# V1_0_0.net
KiCad netlist of a schematic drawn in EAGLE
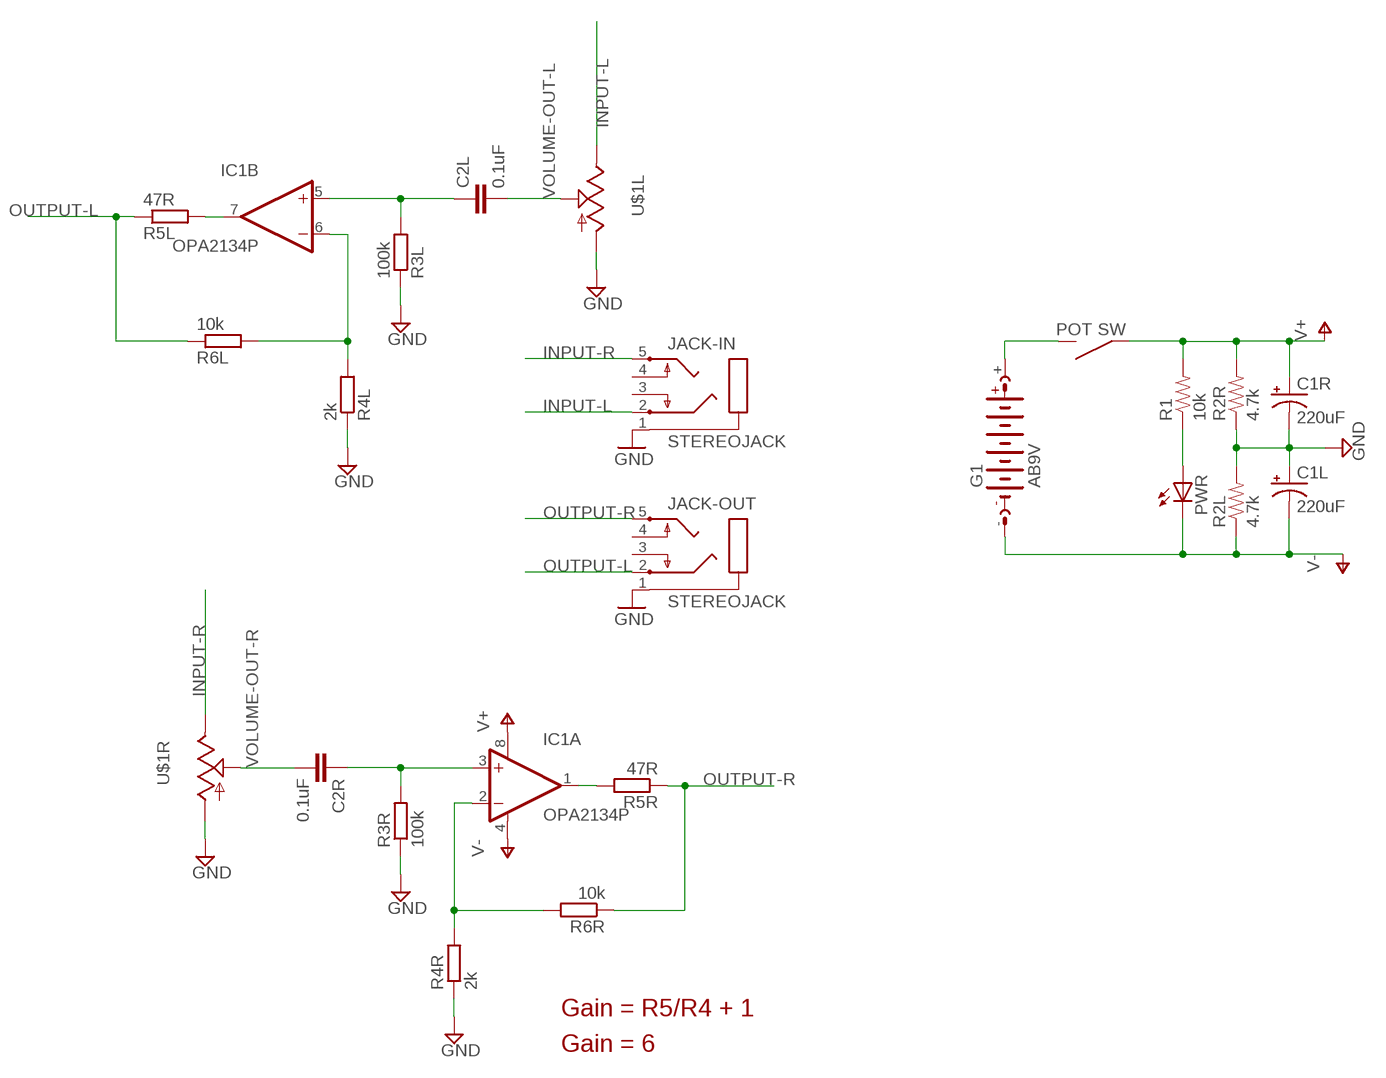
[diagram p0: schematic, sheet 1]

(export (version "E")
  (design (tool "Eeschema 10.0.6"))
  (components
    (comp (ref "C1L")
      (value "220uF")
      (footprint "eagle-import:CPOL-RADIAL-6.3MM")
      (libsource (lib "eagle-import") (part "CAP_POL-RADIAL-6.3MM"))
    )
    (comp (ref "C1R")
      (value "220uF")
      (footprint "eagle-import:CPOL-RADIAL-6.3MM")
      (libsource (lib "eagle-import") (part "CAP_POL-RADIAL-6.3MM"))
    )
    (comp (ref "C2L")
      (value "0.1uF")
      (footprint "eagle-import:C5B5")
      (libsource (lib "eagle-import") (part "C5/5"))
    )
    (comp (ref "C2R")
      (value "0.1uF")
      (footprint "eagle-import:C5B5")
      (libsource (lib "eagle-import") (part "C5/5"))
    )
    (comp (ref "G1")
      (value "AB9V")
      (footprint "eagle-import:AB9V")
      (libsource (lib "eagle-import") (part "AB9V"))
    )
    (comp (ref "IC1")
      (value "OPA2134P")
      (footprint "eagle-import:DIL-8")
      (libsource (lib "eagle-import") (part "OPA2134P"))
    )
    (comp (ref "JACK-IN")
      (value "STEREOJACK")
      (footprint "eagle-import:STX3100")
      (libsource (lib "eagle-import") (part "STEREOJACK"))
    )
    (comp (ref "JACK-OUT")
      (value "STEREOJACK")
      (footprint "eagle-import:STX3100")
      (libsource (lib "eagle-import") (part "STEREOJACK"))
    )
    (comp (ref "PWR")
      (value "LED-3MM-MINUS")
      (footprint "eagle-import:LED3MM-MINUS")
      (libsource (lib "eagle-import") (part "LED-3MM-MINUS"))
    )
    (comp (ref "R1")
      (value "10k")
      (footprint "eagle-import:1_6W-RES-OUTLINE")
      (libsource (lib "eagle-import") (part "RESISTOR-PTH-1/6W-OUTLINE"))
    )
    (comp (ref "R2L")
      (value "4.7k")
      (footprint "eagle-import:1_6W-RES-OUTLINE")
      (libsource (lib "eagle-import") (part "RESISTOR-PTH-1/6W-OUTLINE"))
    )
    (comp (ref "R2R")
      (value "4.7k")
      (footprint "eagle-import:1_6W-RES-OUTLINE")
      (libsource (lib "eagle-import") (part "RESISTOR-PTH-1/6W-OUTLINE"))
    )
    (comp (ref "R3L")
      (value "100k")
      (footprint "eagle-import:0207_2V")
      (libsource (lib "eagle-import") (part "R-EU_0207/2V"))
    )
    (comp (ref "R3R")
      (value "100k")
      (footprint "eagle-import:0207_2V")
      (libsource (lib "eagle-import") (part "R-EU_0207/2V"))
    )
    (comp (ref "R4L")
      (value "2k")
      (footprint "eagle-import:0207_2V")
      (libsource (lib "eagle-import") (part "R-EU_0207/2V"))
    )
    (comp (ref "R4R")
      (value "2k")
      (footprint "eagle-import:0207_2V")
      (libsource (lib "eagle-import") (part "R-EU_0207/2V"))
    )
    (comp (ref "R5L")
      (value "47R")
      (footprint "eagle-import:0207_2V")
      (libsource (lib "eagle-import") (part "R-EU_0207/2V"))
    )
    (comp (ref "R5R")
      (value "47R")
      (footprint "eagle-import:0207_2V")
      (libsource (lib "eagle-import") (part "R-EU_0207/2V"))
    )
    (comp (ref "R6L")
      (value "10k")
      (footprint "eagle-import:0207_2V")
      (libsource (lib "eagle-import") (part "R-EU_0207/2V"))
    )
    (comp (ref "R6R")
      (value "10k")
      (footprint "eagle-import:0207_2V")
      (libsource (lib "eagle-import") (part "R-EU_0207/2V"))
    )
    (comp (ref "U$1")
      (value "ALPS_RK0971221Z05")
      (footprint "eagle-import:ALPS_RK0971221Z0X")
      (libsource (lib "eagle-import") (part "ALPS_RK0971221Z05"))
    )
  )
  (nets
    (net (code "1") (name "/INPUT-L") (class "Default")
      (node (ref "JACK-IN") (pin "2") (pinfunction "2_2") (pintype "passive"))
      (node (ref "U$1") (pin "I1") (pinfunction "3_I1") (pintype "passive"))
    )
    (net (code "2") (name "/INPUT-R") (class "Default")
      (node (ref "JACK-IN") (pin "5") (pinfunction "5_5") (pintype "passive"))
      (node (ref "U$1") (pin "I2") (pinfunction "3_I2") (pintype "passive"))
    )
    (net (code "3") (name "/OUTPUT-L") (class "Default")
      (node (ref "JACK-OUT") (pin "2") (pinfunction "2_2") (pintype "passive"))
      (node (ref "R5L") (pin "1") (pinfunction "1_1") (pintype "passive"))
      (node (ref "R6L") (pin "1") (pinfunction "1_1") (pintype "passive"))
    )
    (net (code "4") (name "/OUTPUT-R") (class "Default")
      (node (ref "JACK-OUT") (pin "5") (pinfunction "5_5") (pintype "passive"))
      (node (ref "R5R") (pin "1") (pinfunction "1_1") (pintype "passive"))
      (node (ref "R6R") (pin "1") (pinfunction "1_1") (pintype "passive"))
    )
    (net (code "5") (name "/VOLUME-OUT-L") (class "Default")
      (node (ref "C2L") (pin "2") (pinfunction "2_2") (pintype "passive"))
      (node (ref "U$1") (pin "O1") (pinfunction "2_O1") (pintype "passive"))
    )
    (net (code "6") (name "/VOLUME-OUT-R") (class "Default")
      (node (ref "C2R") (pin "2") (pinfunction "2_2") (pintype "passive"))
      (node (ref "U$1") (pin "O2") (pinfunction "2_O2") (pintype "passive"))
    )
    (net (code "7") (name "GND") (class "Default")
      (node (ref "C1L") (pin "1") (pinfunction "+_1") (pintype "passive"))
      (node (ref "C1R") (pin "2") (pinfunction "-_2") (pintype "passive"))
      (node (ref "JACK-IN") (pin "1") (pinfunction "1_1") (pintype "passive"))
      (node (ref "JACK-OUT") (pin "1") (pinfunction "1_1") (pintype "passive"))
      (node (ref "R2L") (pin "2") (pinfunction "2_2") (pintype "passive"))
      (node (ref "R2R") (pin "1") (pinfunction "1_1") (pintype "passive"))
      (node (ref "R3L") (pin "1") (pinfunction "1_1") (pintype "passive"))
      (node (ref "R3R") (pin "1") (pinfunction "1_1") (pintype "passive"))
      (node (ref "R4L") (pin "1") (pinfunction "1_1") (pintype "passive"))
      (node (ref "R4R") (pin "1") (pinfunction "1_1") (pintype "passive"))
      (node (ref "U$1") (pin "G1") (pinfunction "1_G1") (pintype "passive"))
      (node (ref "U$1") (pin "G2") (pinfunction "1_G2") (pintype "passive"))
    )
    (net (code "8") (name "Net-(G1-Pad+)") (class "Default")
      (node (ref "G1") (pin "+") (pinfunction "+_+") (pintype "passive"))
      (node (ref "U$1") (pin "S2") (pinfunction "S2_S2") (pintype "power_in"))
    )
    (net (code "9") (name "Net-(IC1A-+IN)") (class "Default")
      (node (ref "C2R") (pin "1") (pinfunction "1_1") (pintype "passive"))
      (node (ref "IC1") (pin "3") (pinfunction "+IN_3") (pintype "input"))
      (node (ref "R3R") (pin "2") (pinfunction "2_2") (pintype "passive"))
    )
    (net (code "10") (name "Net-(IC1A--IN)") (class "Default")
      (node (ref "IC1") (pin "2") (pinfunction "-IN_2") (pintype "input"))
      (node (ref "R4R") (pin "2") (pinfunction "2_2") (pintype "passive"))
      (node (ref "R6R") (pin "2") (pinfunction "2_2") (pintype "passive"))
    )
    (net (code "11") (name "Net-(IC1A-OUT)") (class "Default")
      (node (ref "IC1") (pin "1") (pinfunction "OUT_1") (pintype "output"))
      (node (ref "R5R") (pin "2") (pinfunction "2_2") (pintype "passive"))
    )
    (net (code "12") (name "Net-(IC1B-+IN)") (class "Default")
      (node (ref "C2L") (pin "1") (pinfunction "1_1") (pintype "passive"))
      (node (ref "IC1") (pin "5") (pinfunction "+IN_5") (pintype "input"))
      (node (ref "R3L") (pin "2") (pinfunction "2_2") (pintype "passive"))
    )
    (net (code "13") (name "Net-(IC1B--IN)") (class "Default")
      (node (ref "IC1") (pin "6") (pinfunction "-IN_6") (pintype "input"))
      (node (ref "R4L") (pin "2") (pinfunction "2_2") (pintype "passive"))
      (node (ref "R6L") (pin "2") (pinfunction "2_2") (pintype "passive"))
    )
    (net (code "14") (name "Net-(IC1B-OUT)") (class "Default")
      (node (ref "IC1") (pin "7") (pinfunction "OUT_7") (pintype "output"))
      (node (ref "R5L") (pin "2") (pinfunction "2_2") (pintype "passive"))
    )
    (net (code "15") (name "Net-(PWR-PadA)") (class "Default")
      (node (ref "PWR") (pin "A") (pinfunction "A_A") (pintype "passive"))
      (node (ref "R1") (pin "1") (pinfunction "1_1") (pintype "passive"))
    )
    (net (code "16") (name "V+") (class "Default")
      (node (ref "C1R") (pin "1") (pinfunction "+_1") (pintype "passive"))
      (node (ref "IC1") (pin "8") (pinfunction "V+_8") (pintype "power_in"))
      (node (ref "R1") (pin "2") (pinfunction "2_2") (pintype "passive"))
      (node (ref "R2R") (pin "2") (pinfunction "2_2") (pintype "passive"))
      (node (ref "U$1") (pin "S1") (pinfunction "S1_S1") (pintype "power_in"))
    )
    (net (code "17") (name "V-") (class "Default")
      (node (ref "C1L") (pin "2") (pinfunction "-_2") (pintype "passive"))
      (node (ref "G1") (pin "-") (pinfunction "-_-") (pintype "passive"))
      (node (ref "IC1") (pin "4") (pinfunction "V-_4") (pintype "power_in"))
      (node (ref "PWR") (pin "K") (pinfunction "C_K") (pintype "passive"))
      (node (ref "R2L") (pin "1") (pinfunction "1_1") (pintype "passive"))
    )
    (net (code "18") (name "unconnected-(JACK-IN-Pad3)") (class "Default")
      (node (ref "JACK-IN") (pin "3") (pinfunction "3_3") (pintype "passive"))
    )
    (net (code "19") (name "unconnected-(JACK-IN-Pad4)") (class "Default")
      (node (ref "JACK-IN") (pin "4") (pinfunction "4_4") (pintype "passive"))
    )
    (net (code "20") (name "unconnected-(JACK-OUT-Pad3)") (class "Default")
      (node (ref "JACK-OUT") (pin "3") (pinfunction "3_3") (pintype "passive"))
    )
    (net (code "21") (name "unconnected-(JACK-OUT-Pad4)") (class "Default")
      (node (ref "JACK-OUT") (pin "4") (pinfunction "4_4") (pintype "passive"))
    )
  )
)
